# schematic.net
KiCad netlist of a schematic drawn in EasyEDA
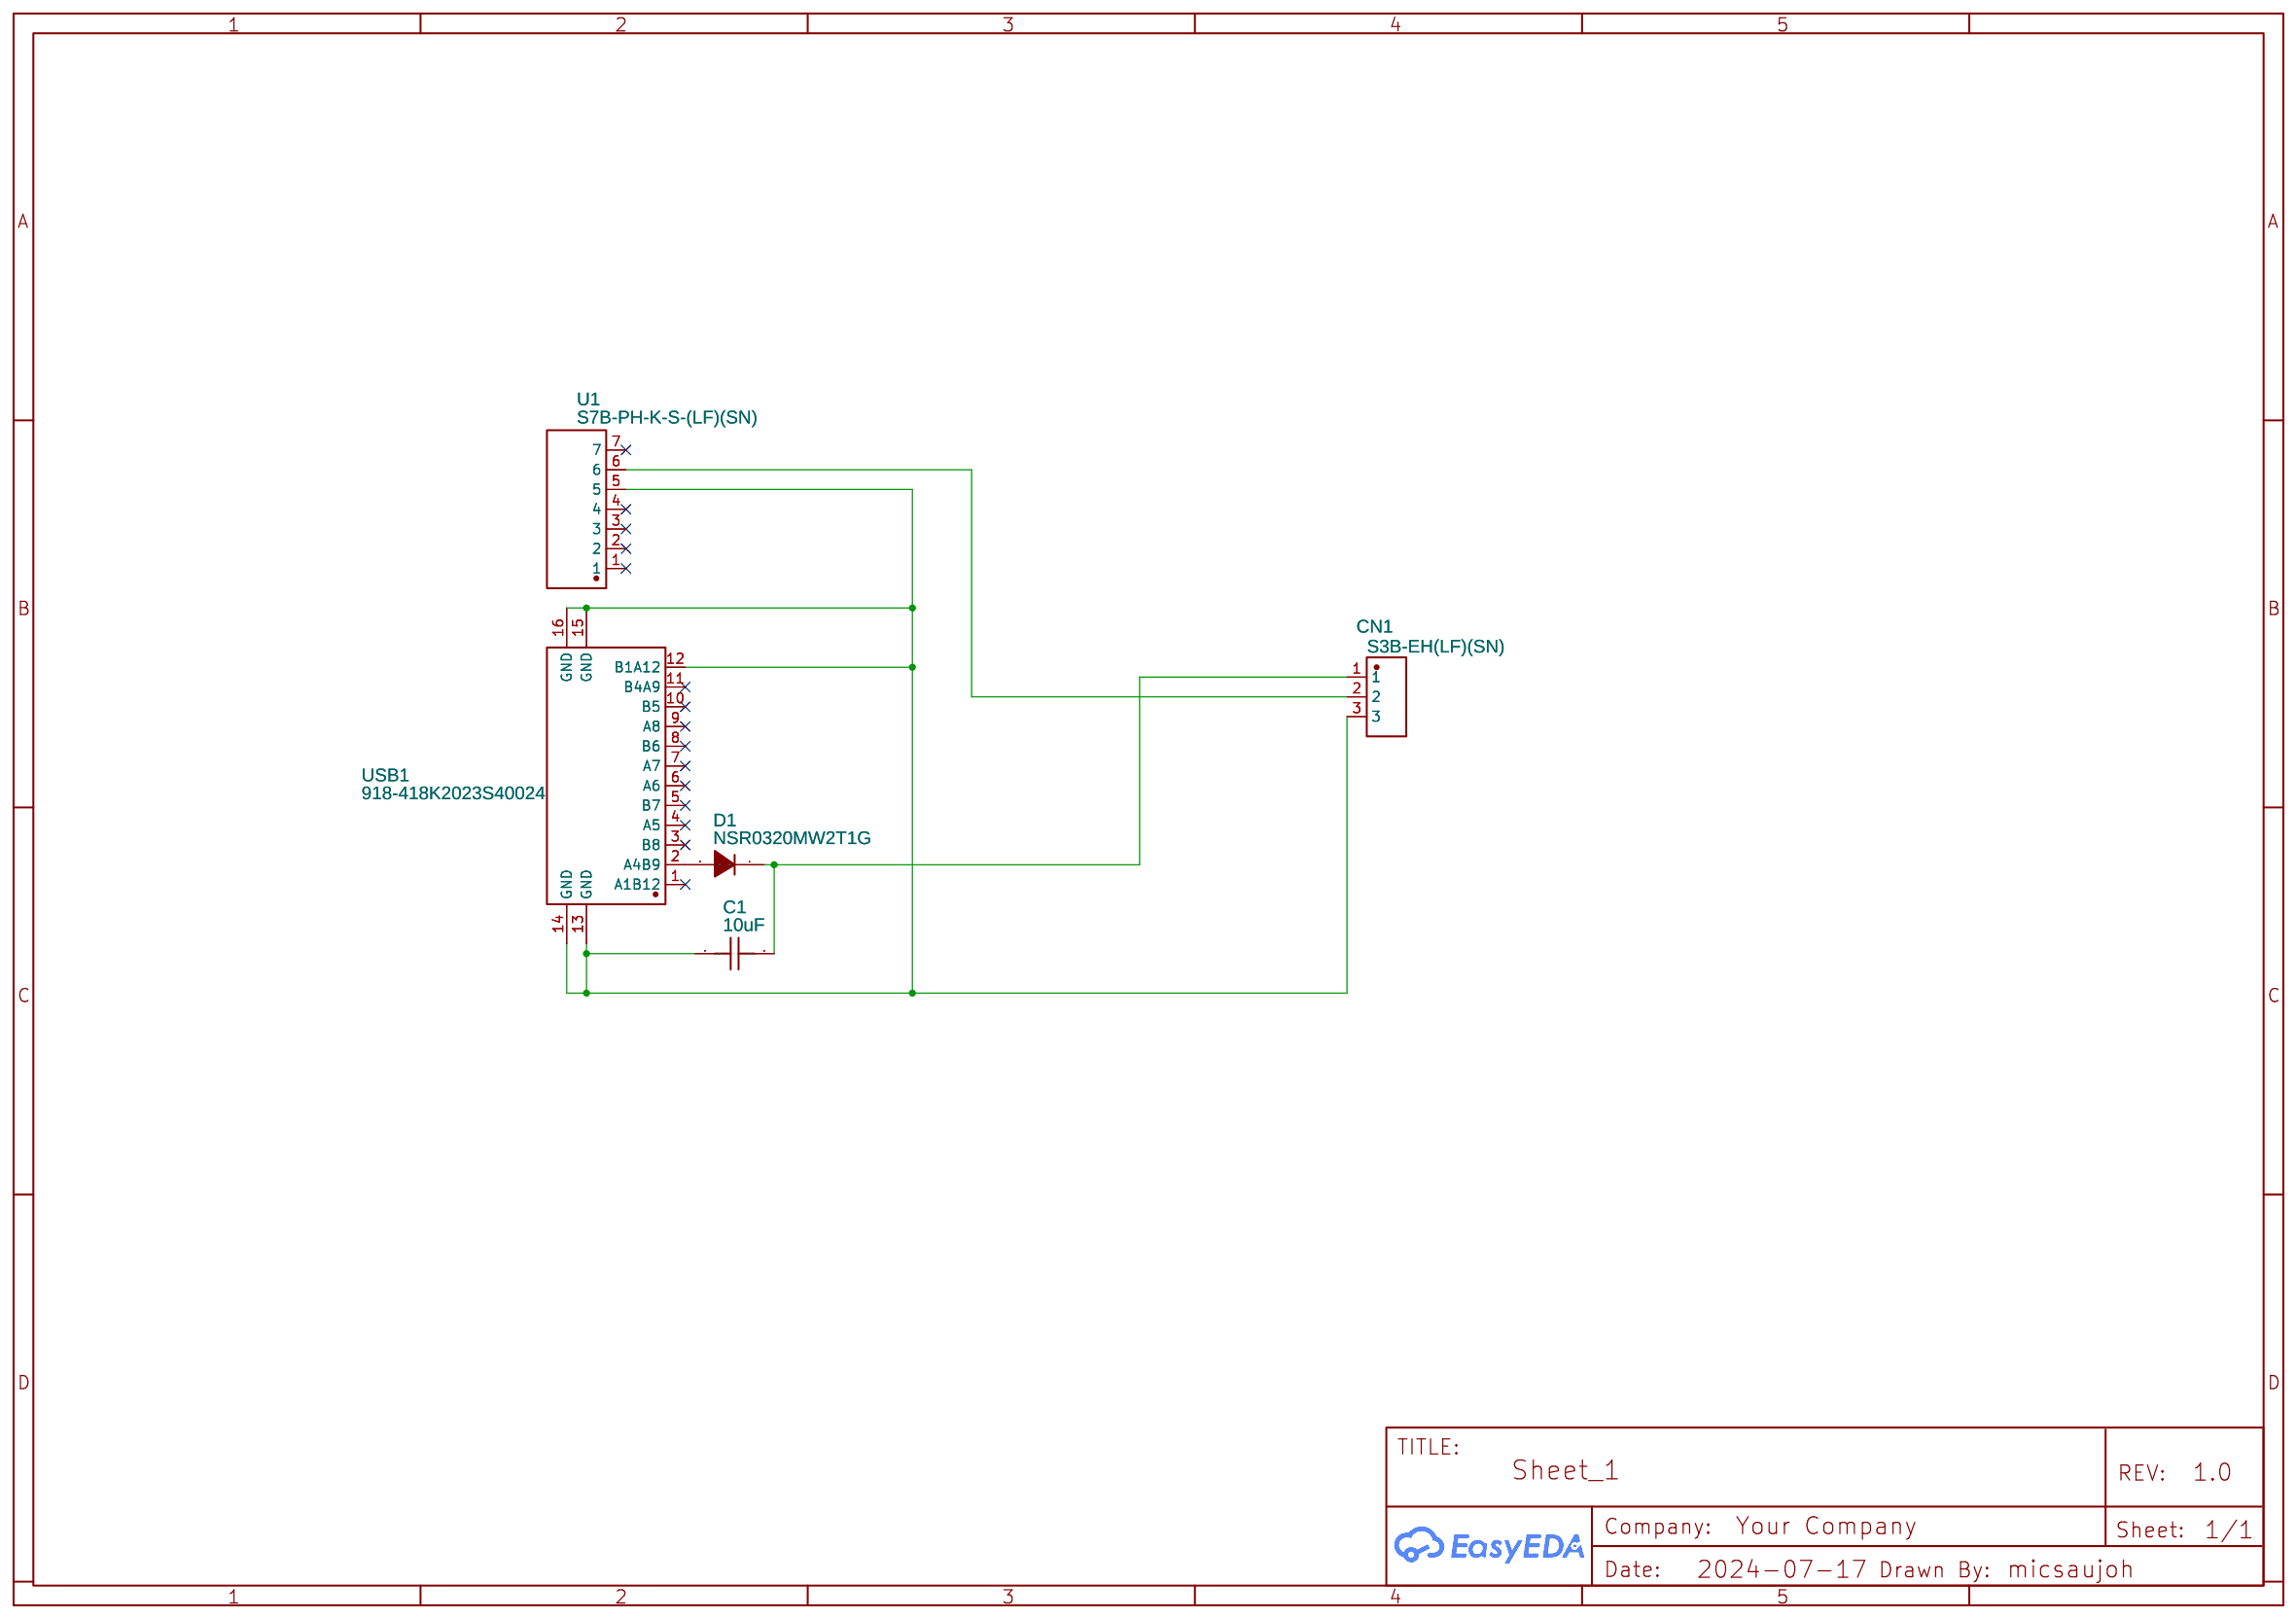
[diagram p0: schematic sheet]

(export (version "E")
  (design (tool "Eeschema 10.0.6"))
  (components
    (comp (ref "C1")
      (value "10uF")
      (fields
        (field (name "Manufacturer Part") "CL10A106KP8NNNC")
        (field (name "Manufacturer") "SAMSUNG(三星)")
      )
      (libsource (lib "") (part "CL10A106KP8NNNC"))
    )
    (comp (ref "CN1")
      (value "S3B-EH(LF)(SN)")
      (fields (field (name "Manufacturer") "JST"))
      (libsource (lib "") (part "S3B-EH(LF)(SN)"))
    )
    (comp (ref "D1")
      (value "NSR0320MW2T1G")
      (fields (field (name "Manufacturer") "onsemi(安森美)"))
      (libsource (lib "") (part "NSR0320MW2T1G"))
    )
    (comp (ref "U1")
      (value "S7B-PH-K-S-(LF)(SN)")
      (fields (field (name "Manufacturer Part") "S7B-PH-K-S(LF)(SN)") (field (name "Manufacturer") "JST"))
      (libsource (lib "") (part "S7B-PH-K-S-(LF)(SN)"))
    )
    (comp (ref "USB1")
      (value "918-418K2023S40024")
      (fields (field (name "Manufacturer") "精拓金"))
      (libsource (lib "") (part "918-418K2023S40024"))
    )
  )
  (nets
    (net (code "1") (name "Net-(CN1-Pad2)") (class "Default")
      (node (ref "CN1") (pin "2") (pinfunction "2_2") (pintype "unspecified"))
      (node (ref "U1") (pin "6") (pinfunction "6_6") (pintype "unspecified"))
    )
    (net (code "2") (name "Net-(D1-A)") (class "Default")
      (node (ref "D1") (pin "2") (pinfunction "A_2") (pintype "unspecified"))
      (node (ref "USB1") (pin "2") (pinfunction "A4B9_2") (pintype "unspecified"))
    )
    (net (code "3") (name "Net-(D1-C)") (class "Default")
      (node (ref "C1") (pin "2") (pinfunction "2_2") (pintype "unspecified"))
      (node (ref "CN1") (pin "1") (pinfunction "1_1") (pintype "unspecified"))
      (node (ref "D1") (pin "1") (pinfunction "C_1") (pintype "unspecified"))
    )
    (net (code "4") (name "Net-(USB1-B1A12)") (class "Default")
      (node (ref "C1") (pin "1") (pinfunction "1_1") (pintype "unspecified"))
      (node (ref "CN1") (pin "3") (pinfunction "3_3") (pintype "unspecified"))
      (node (ref "U1") (pin "5") (pinfunction "5_5") (pintype "unspecified"))
      (node (ref "USB1") (pin "12") (pinfunction "B1A12_12") (pintype "unspecified"))
      (node (ref "USB1") (pin "13") (pinfunction "GND_13") (pintype "unspecified"))
      (node (ref "USB1") (pin "14") (pinfunction "GND_14") (pintype "unspecified"))
      (node (ref "USB1") (pin "15") (pinfunction "GND_15") (pintype "unspecified"))
      (node (ref "USB1") (pin "16") (pinfunction "GND_16") (pintype "unspecified"))
    )
    (net (code "5") (name "unconnected-(U1-Pad1)") (class "Default")
      (node (ref "U1") (pin "1") (pinfunction "1_1") (pintype "unspecified+no_connect"))
    )
    (net (code "6") (name "unconnected-(U1-Pad2)") (class "Default")
      (node (ref "U1") (pin "2") (pinfunction "2_2") (pintype "unspecified+no_connect"))
    )
    (net (code "7") (name "unconnected-(U1-Pad3)") (class "Default")
      (node (ref "U1") (pin "3") (pinfunction "3_3") (pintype "unspecified+no_connect"))
    )
    (net (code "8") (name "unconnected-(U1-Pad4)") (class "Default")
      (node (ref "U1") (pin "4") (pinfunction "4_4") (pintype "unspecified+no_connect"))
    )
    (net (code "9") (name "unconnected-(U1-Pad7)") (class "Default")
      (node (ref "U1") (pin "7") (pinfunction "7_7") (pintype "unspecified+no_connect"))
    )
    (net (code "10") (name "unconnected-(USB1-A1B12-Pad1)") (class "Default")
      (node (ref "USB1") (pin "1") (pinfunction "A1B12_1") (pintype "unspecified+no_connect"))
    )
    (net (code "11") (name "unconnected-(USB1-A5-Pad4)") (class "Default")
      (node (ref "USB1") (pin "4") (pinfunction "A5_4") (pintype "unspecified+no_connect"))
    )
    (net (code "12") (name "unconnected-(USB1-A6-Pad6)") (class "Default")
      (node (ref "USB1") (pin "6") (pinfunction "A6_6") (pintype "unspecified+no_connect"))
    )
    (net (code "13") (name "unconnected-(USB1-A7-Pad7)") (class "Default")
      (node (ref "USB1") (pin "7") (pinfunction "A7_7") (pintype "unspecified+no_connect"))
    )
    (net (code "14") (name "unconnected-(USB1-A8-Pad9)") (class "Default")
      (node (ref "USB1") (pin "9") (pinfunction "A8_9") (pintype "unspecified+no_connect"))
    )
    (net (code "15") (name "unconnected-(USB1-B4A9-Pad11)") (class "Default")
      (node (ref "USB1") (pin "11") (pinfunction "B4A9_11") (pintype "unspecified+no_connect"))
    )
    (net (code "16") (name "unconnected-(USB1-B5-Pad10)") (class "Default")
      (node (ref "USB1") (pin "10") (pinfunction "B5_10") (pintype "unspecified+no_connect"))
    )
    (net (code "17") (name "unconnected-(USB1-B6-Pad8)") (class "Default")
      (node (ref "USB1") (pin "8") (pinfunction "B6_8") (pintype "unspecified+no_connect"))
    )
    (net (code "18") (name "unconnected-(USB1-B7-Pad5)") (class "Default")
      (node (ref "USB1") (pin "5") (pinfunction "B7_5") (pintype "unspecified+no_connect"))
    )
    (net (code "19") (name "unconnected-(USB1-B8-Pad3)") (class "Default")
      (node (ref "USB1") (pin "3") (pinfunction "B8_3") (pintype "unspecified+no_connect"))
    )
  )
)
